# DCDCFinalBoardLayout.net
KiCad netlist of a schematic drawn in EAGLE
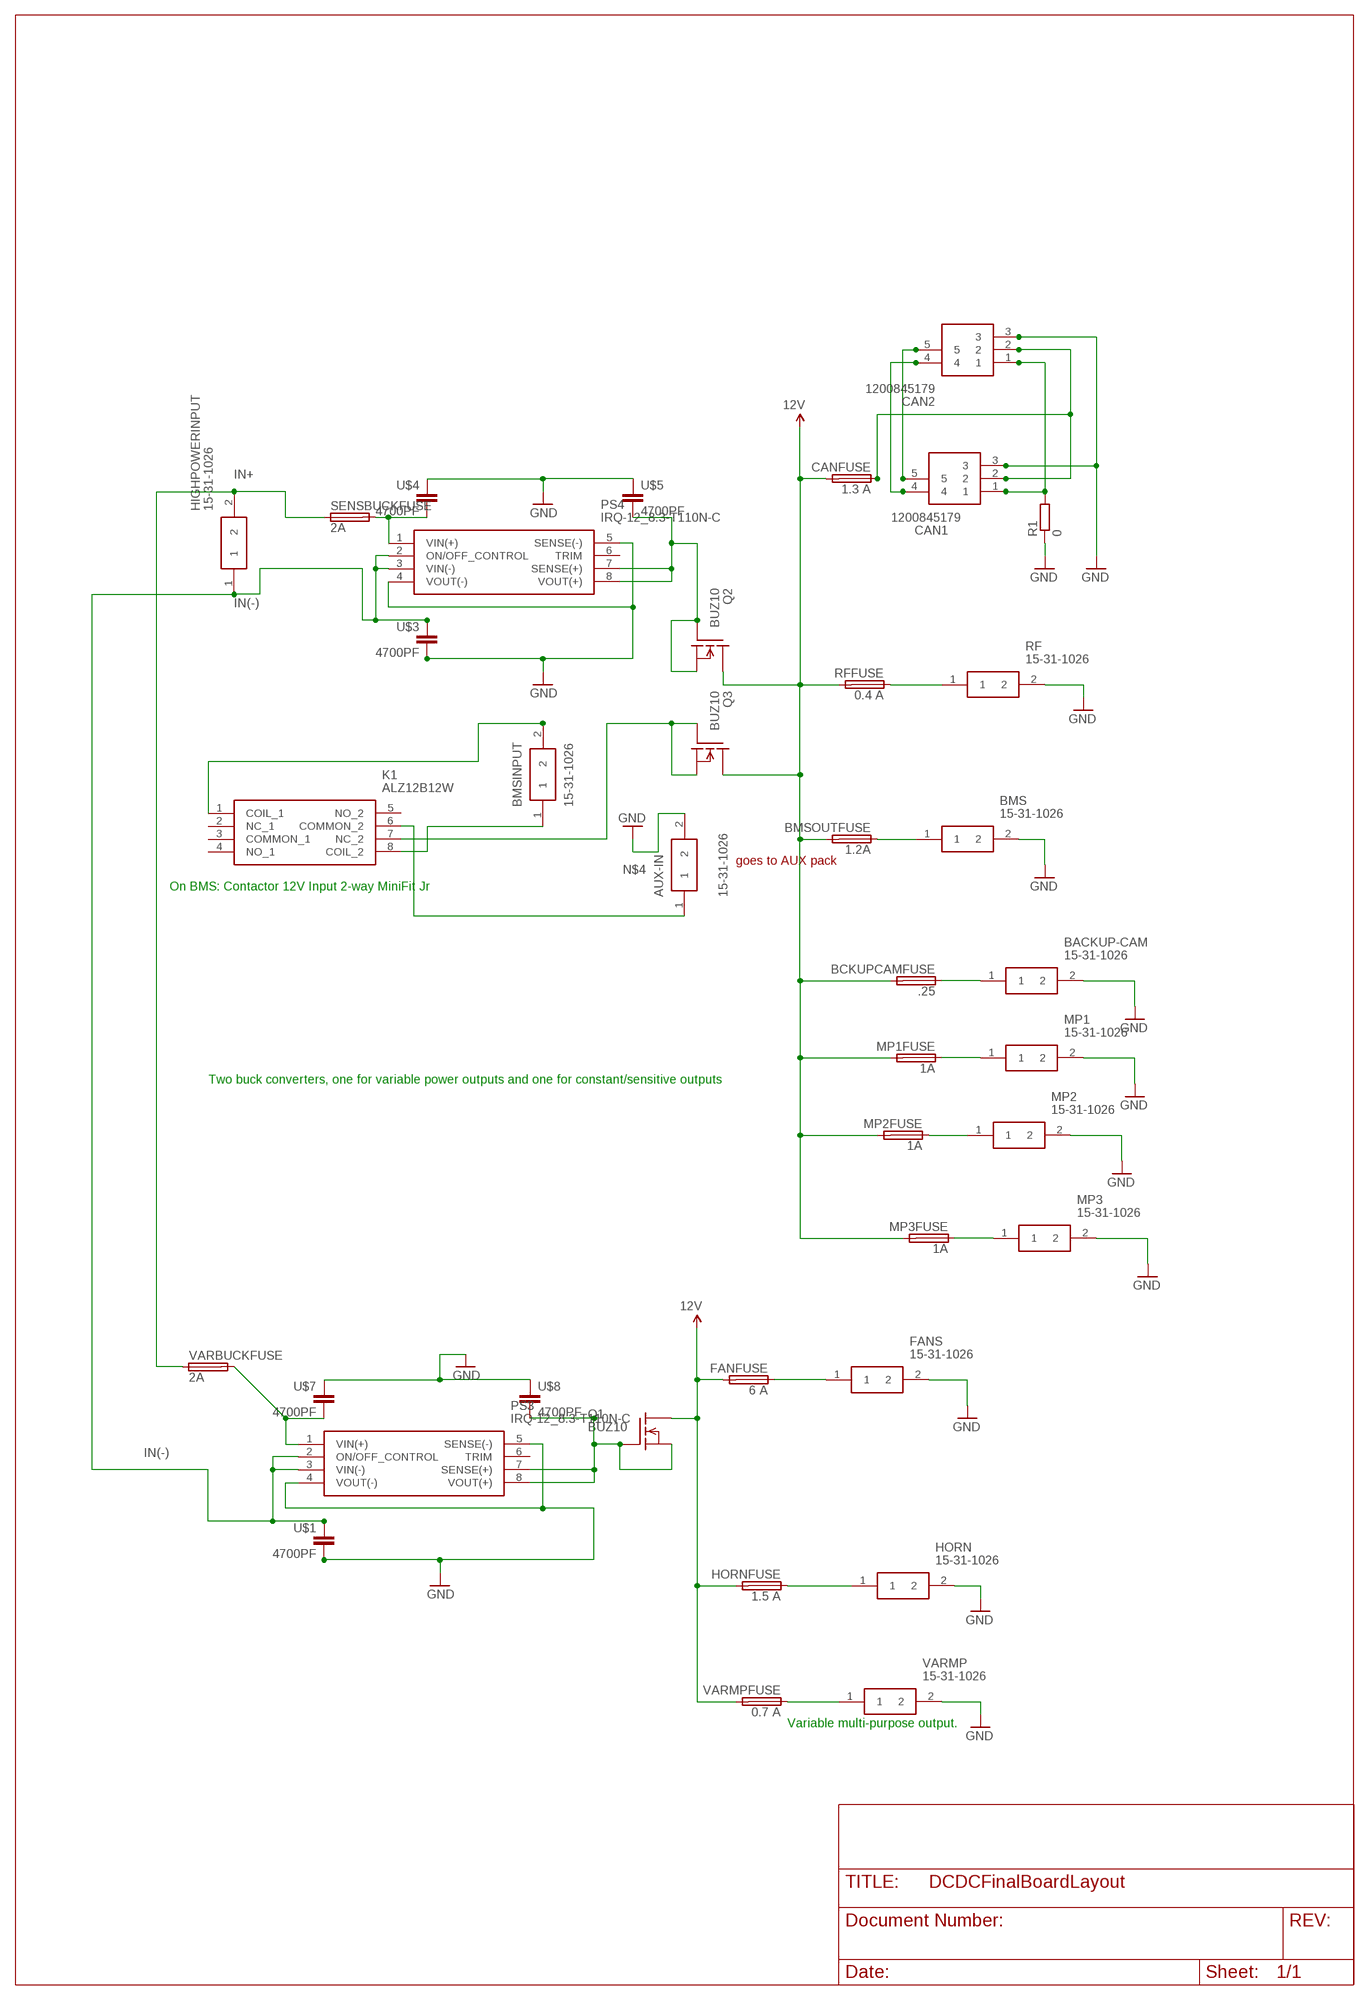
[diagram p0: schematic, sheet 1]

(export (version "E")
  (design (tool "Eeschema 10.0.6"))
  (components
    (comp (ref "AUX-IN")
      (value "15-31-1026")
      (footprint "eagle-import:15311026")
      (fields (field (name "MOUSER_PART_NUMBER") "538-15-31-1026"))
      (libsource (lib "eagle-import") (part "15-31-1026"))
    )
    (comp (ref "BACKUP-CAM")
      (value "15-31-1026")
      (footprint "eagle-import:15311026")
      (fields (field (name "MOUSER_PART_NUMBER") "538-15-31-1026"))
      (libsource (lib "eagle-import") (part "15-31-1026"))
    )
    (comp (ref "BCKUPCAMFUSE")
      (value ".25")
      (footprint "eagle-import:OMNIBLOK")
      (libsource (lib "eagle-import") (part "SMD-MICRO-FUSE-BLOCK"))
    )
    (comp (ref "BMS")
      (value "15-31-1026")
      (footprint "eagle-import:15311026")
      (fields (field (name "MOUSER_PART_NUMBER") "538-15-31-1026"))
      (libsource (lib "eagle-import") (part "15-31-1026"))
    )
    (comp (ref "BMSINPUT")
      (value "15-31-1026")
      (footprint "eagle-import:15311026")
      (fields (field (name "MOUSER_PART_NUMBER") "538-15-31-1026"))
      (libsource (lib "eagle-import") (part "15-31-1026"))
    )
    (comp (ref "BMSOUTFUSE")
      (value "1.2A")
      (footprint "eagle-import:OMNIBLOK")
      (libsource (lib "eagle-import") (part "SMD-MICRO-FUSE-BLOCK"))
    )
    (comp (ref "CAN1")
      (value "1200845179")
      (footprint "eagle-import:1200845179")
      (fields (field (name "MOUSER_PART_NUMBER") "538-1200845179"))
      (libsource (lib "eagle-import") (part "1200845179"))
    )
    (comp (ref "CAN2")
      (value "1200845179")
      (footprint "eagle-import:1200845179")
      (fields (field (name "MOUSER_PART_NUMBER") "538-1200845179"))
      (libsource (lib "eagle-import") (part "1200845179"))
    )
    (comp (ref "CANFUSE")
      (value "1.3 A")
      (footprint "eagle-import:OMNIBLOK")
      (libsource (lib "eagle-import") (part "SMD-MICRO-FUSE-BLOCK"))
    )
    (comp (ref "FANFUSE")
      (value "6 A")
      (footprint "eagle-import:OMNIBLOK")
      (libsource (lib "eagle-import") (part "SMD-MICRO-FUSE-BLOCK"))
    )
    (comp (ref "FANS")
      (value "15-31-1026")
      (footprint "eagle-import:15311026")
      (fields (field (name "MOUSER_PART_NUMBER") "538-15-31-1026"))
      (libsource (lib "eagle-import") (part "15-31-1026"))
    )
    (comp (ref "HIGHPOWERINPUT")
      (value "15-31-1026")
      (footprint "eagle-import:15311026")
      (fields (field (name "MOUSER_PART_NUMBER") "538-15-31-1026"))
      (libsource (lib "eagle-import") (part "15-31-1026"))
    )
    (comp (ref "HORN")
      (value "15-31-1026")
      (footprint "eagle-import:15311026")
      (fields (field (name "MOUSER_PART_NUMBER") "538-15-31-1026"))
      (libsource (lib "eagle-import") (part "15-31-1026"))
    )
    (comp (ref "HORNFUSE")
      (value "1.5 A")
      (footprint "eagle-import:OMNIBLOK")
      (libsource (lib "eagle-import") (part "SMD-MICRO-FUSE-BLOCK"))
    )
    (comp (ref "K1")
      (value "ALZ12B12W")
      (footprint "eagle-import:ALZ12B12W")
      (libsource (lib "eagle-import") (part "ALZ12B12W"))
    )
    (comp (ref "MP1")
      (value "15-31-1026")
      (footprint "eagle-import:15311026")
      (fields (field (name "MOUSER_PART_NUMBER") "538-15-31-1026"))
      (libsource (lib "eagle-import") (part "15-31-1026"))
    )
    (comp (ref "MP1FUSE")
      (value "1A")
      (footprint "eagle-import:OMNIBLOK")
      (libsource (lib "eagle-import") (part "SMD-MICRO-FUSE-BLOCK"))
    )
    (comp (ref "MP2")
      (value "15-31-1026")
      (footprint "eagle-import:15311026")
      (fields (field (name "MOUSER_PART_NUMBER") "538-15-31-1026"))
      (libsource (lib "eagle-import") (part "15-31-1026"))
    )
    (comp (ref "MP2FUSE")
      (value "1A")
      (footprint "eagle-import:OMNIBLOK")
      (libsource (lib "eagle-import") (part "SMD-MICRO-FUSE-BLOCK"))
    )
    (comp (ref "MP3")
      (value "15-31-1026")
      (footprint "eagle-import:15311026")
      (fields (field (name "MOUSER_PART_NUMBER") "538-15-31-1026"))
      (libsource (lib "eagle-import") (part "15-31-1026"))
    )
    (comp (ref "MP3FUSE")
      (value "1A")
      (footprint "eagle-import:OMNIBLOK")
      (libsource (lib "eagle-import") (part "SMD-MICRO-FUSE-BLOCK"))
    )
    (comp (ref "PS3")
      (value "IRQ-12_8.3-T110N-C")
      (footprint "eagle-import:IRQ1283T110NC")
      (fields
        (field (name "MANUFACTURER_PART_NUMBER") "IRQ-12/8.3-T110N-C")
        (field (name "MOUSER_PART_NUMBER") "580-IRQ-12/8.3T110NC")
      )
      (libsource (lib "eagle-import") (part "IRQ-12_8.3-T110N-C"))
    )
    (comp (ref "PS4")
      (value "IRQ-12_8.3-T110N-C")
      (footprint "eagle-import:IRQ1283T110NC")
      (fields
        (field (name "MANUFACTURER_PART_NUMBER") "IRQ-12/8.3-T110N-C")
        (field (name "MOUSER_PART_NUMBER") "580-IRQ-12/8.3T110NC")
      )
      (libsource (lib "eagle-import") (part "IRQ-12_8.3-T110N-C"))
    )
    (comp (ref "Q1")
      (value "BUZ10")
      (footprint "eagle-import:TO220")
      (libsource (lib "eagle-import") (part "BUZ10"))
    )
    (comp (ref "Q2")
      (value "BUZ10")
      (footprint "eagle-import:TO220")
      (libsource (lib "eagle-import") (part "BUZ10"))
    )
    (comp (ref "Q3")
      (value "BUZ10")
      (footprint "eagle-import:TO220")
      (libsource (lib "eagle-import") (part "BUZ10"))
    )
    (comp (ref "R1") (value "0") (footprint "eagle-import:R0805") (libsource (lib "eagle-import") (part "R")))
    (comp (ref "RF")
      (value "15-31-1026")
      (footprint "eagle-import:15311026")
      (fields (field (name "MOUSER_PART_NUMBER") "538-15-31-1026"))
      (libsource (lib "eagle-import") (part "15-31-1026"))
    )
    (comp (ref "RFFUSE")
      (value "0.4 A")
      (footprint "eagle-import:OMNIBLOK")
      (libsource (lib "eagle-import") (part "SMD-MICRO-FUSE-BLOCK"))
    )
    (comp (ref "SENSBUCKFUSE")
      (value "2A")
      (footprint "eagle-import:OMNIBLOK")
      (libsource (lib "eagle-import") (part "SMD-MICRO-FUSE-BLOCK"))
    )
    (comp (ref "U$1")
      (value "4700PF")
      (footprint "eagle-import:Y2_CAP")
      (libsource (lib "eagle-import") (part "4700PF"))
    )
    (comp (ref "U$3")
      (value "4700PF")
      (footprint "eagle-import:Y2_CAP")
      (libsource (lib "eagle-import") (part "4700PF"))
    )
    (comp (ref "U$4")
      (value "4700PF")
      (footprint "eagle-import:Y2_CAP")
      (libsource (lib "eagle-import") (part "4700PF"))
    )
    (comp (ref "U$5")
      (value "4700PF")
      (footprint "eagle-import:Y2_CAP")
      (libsource (lib "eagle-import") (part "4700PF"))
    )
    (comp (ref "U$7")
      (value "4700PF")
      (footprint "eagle-import:Y2_CAP")
      (libsource (lib "eagle-import") (part "4700PF"))
    )
    (comp (ref "U$8")
      (value "4700PF")
      (footprint "eagle-import:Y2_CAP")
      (libsource (lib "eagle-import") (part "4700PF"))
    )
    (comp (ref "VARBUCKFUSE")
      (value "2A")
      (footprint "eagle-import:OMNIBLOK")
      (libsource (lib "eagle-import") (part "SMD-MICRO-FUSE-BLOCK"))
    )
    (comp (ref "VARMP")
      (value "15-31-1026")
      (footprint "eagle-import:15311026")
      (fields (field (name "MOUSER_PART_NUMBER") "538-15-31-1026"))
      (libsource (lib "eagle-import") (part "15-31-1026"))
    )
    (comp (ref "VARMPFUSE")
      (value "0.7 A")
      (footprint "eagle-import:OMNIBLOK")
      (libsource (lib "eagle-import") (part "SMD-MICRO-FUSE-BLOCK"))
    )
  )
  (nets
    (net (code "1") (name "/IN(-)") (class "Default")
      (node (ref "HIGHPOWERINPUT") (pin "1") (pinfunction "1_1") (pintype "bidirectional"))
      (node (ref "PS3") (pin "2") (pinfunction "ON/OFF_CONTROL_2") (pintype "bidirectional"))
      (node (ref "PS3") (pin "3") (pinfunction "VIN(-)_3") (pintype "bidirectional"))
      (node (ref "PS4") (pin "2") (pinfunction "ON/OFF_CONTROL_2") (pintype "bidirectional"))
      (node (ref "PS4") (pin "3") (pinfunction "VIN(-)_3") (pintype "bidirectional"))
      (node (ref "U$1") (pin "P$1") (pinfunction "1_P$1") (pintype "passive"))
      (node (ref "U$3") (pin "P$1") (pinfunction "1_P$1") (pintype "passive"))
    )
    (net (code "2") (name "/IN+") (class "Default")
      (node (ref "HIGHPOWERINPUT") (pin "2") (pinfunction "2_2") (pintype "bidirectional"))
      (node (ref "SENSBUCKFUSE") (pin "P$1") (pinfunction "1_P$1") (pintype "passive"))
      (node (ref "VARBUCKFUSE") (pin "P$1") (pinfunction "1_P$1") (pintype "passive"))
    )
    (net (code "3") (name "/N$4") (class "Default")
      (node (ref "BMSINPUT") (pin "2") (pinfunction "2_2") (pintype "bidirectional"))
      (node (ref "K1") (pin "1") (pinfunction "COIL_1_1") (pintype "bidirectional"))
      (node (ref "K1") (pin "7") (pinfunction "NC_2_7") (pintype "bidirectional"))
      (node (ref "Q3") (pin "1") (pinfunction "G_1") (pintype "passive"))
      (node (ref "Q3") (pin "3") (pinfunction "S_3") (pintype "passive"))
    )
    (net (code "4") (name "12V") (class "Default")
      (node (ref "BCKUPCAMFUSE") (pin "P$2") (pinfunction "2_P$2") (pintype "passive"))
      (node (ref "BMSOUTFUSE") (pin "P$2") (pinfunction "2_P$2") (pintype "passive"))
      (node (ref "CANFUSE") (pin "P$2") (pinfunction "2_P$2") (pintype "passive"))
      (node (ref "FANFUSE") (pin "P$2") (pinfunction "2_P$2") (pintype "passive"))
      (node (ref "HORNFUSE") (pin "P$2") (pinfunction "2_P$2") (pintype "passive"))
      (node (ref "MP1FUSE") (pin "P$2") (pinfunction "2_P$2") (pintype "passive"))
      (node (ref "MP2FUSE") (pin "P$2") (pinfunction "2_P$2") (pintype "passive"))
      (node (ref "MP3FUSE") (pin "P$2") (pinfunction "2_P$2") (pintype "passive"))
      (node (ref "Q1") (pin "2") (pinfunction "D_2") (pintype "passive"))
      (node (ref "Q2") (pin "2") (pinfunction "D_2") (pintype "passive"))
      (node (ref "Q3") (pin "2") (pinfunction "D_2") (pintype "passive"))
      (node (ref "RFFUSE") (pin "P$2") (pinfunction "2_P$2") (pintype "passive"))
      (node (ref "VARMPFUSE") (pin "P$2") (pinfunction "2_P$2") (pintype "passive"))
    )
    (net (code "5") (name "GND") (class "Default")
      (node (ref "AUX-IN") (pin "2") (pinfunction "2_2") (pintype "bidirectional"))
      (node (ref "BACKUP-CAM") (pin "2") (pinfunction "2_2") (pintype "bidirectional"))
      (node (ref "BMS") (pin "2") (pinfunction "2_2") (pintype "bidirectional"))
      (node (ref "CAN1") (pin "3") (pinfunction "3_3") (pintype "bidirectional"))
      (node (ref "CAN2") (pin "3") (pinfunction "3_3") (pintype "bidirectional"))
      (node (ref "FANS") (pin "2") (pinfunction "2_2") (pintype "bidirectional"))
      (node (ref "HORN") (pin "2") (pinfunction "2_2") (pintype "bidirectional"))
      (node (ref "MP1") (pin "2") (pinfunction "2_2") (pintype "bidirectional"))
      (node (ref "MP2") (pin "2") (pinfunction "2_2") (pintype "bidirectional"))
      (node (ref "MP3") (pin "2") (pinfunction "2_2") (pintype "bidirectional"))
      (node (ref "PS3") (pin "4") (pinfunction "VOUT(-)_4") (pintype "bidirectional"))
      (node (ref "PS3") (pin "5") (pinfunction "SENSE(-)_5") (pintype "bidirectional"))
      (node (ref "PS4") (pin "4") (pinfunction "VOUT(-)_4") (pintype "bidirectional"))
      (node (ref "PS4") (pin "5") (pinfunction "SENSE(-)_5") (pintype "bidirectional"))
      (node (ref "R1") (pin "1") (pinfunction "1_1") (pintype "passive"))
      (node (ref "RF") (pin "2") (pinfunction "2_2") (pintype "bidirectional"))
      (node (ref "U$1") (pin "P$2") (pinfunction "2_P$2") (pintype "passive"))
      (node (ref "U$3") (pin "P$2") (pinfunction "2_P$2") (pintype "passive"))
      (node (ref "U$4") (pin "P$1") (pinfunction "1_P$1") (pintype "passive"))
      (node (ref "U$5") (pin "P$1") (pinfunction "1_P$1") (pintype "passive"))
      (node (ref "U$7") (pin "P$1") (pinfunction "1_P$1") (pintype "passive"))
      (node (ref "U$8") (pin "P$1") (pinfunction "1_P$1") (pintype "passive"))
      (node (ref "VARMP") (pin "2") (pinfunction "2_2") (pintype "bidirectional"))
    )
    (net (code "6") (name "Net-(BCKUPCAMFUSE-1)") (class "Default")
      (node (ref "BACKUP-CAM") (pin "1") (pinfunction "1_1") (pintype "bidirectional"))
      (node (ref "BCKUPCAMFUSE") (pin "P$1") (pinfunction "1_P$1") (pintype "passive"))
    )
    (net (code "7") (name "Net-(BMSOUTFUSE-1)") (class "Default")
      (node (ref "BMS") (pin "1") (pinfunction "1_1") (pintype "bidirectional"))
      (node (ref "BMSOUTFUSE") (pin "P$1") (pinfunction "1_P$1") (pintype "passive"))
    )
    (net (code "8") (name "Net-(CAN1-Pad1)") (class "Default")
      (node (ref "CAN1") (pin "1") (pinfunction "1_1") (pintype "bidirectional"))
      (node (ref "CAN2") (pin "1") (pinfunction "1_1") (pintype "bidirectional"))
      (node (ref "R1") (pin "2") (pinfunction "2_2") (pintype "passive"))
    )
    (net (code "9") (name "Net-(CAN1-Pad4)") (class "Default")
      (node (ref "CAN1") (pin "4") (pinfunction "4_4") (pintype "bidirectional"))
      (node (ref "CAN2") (pin "4") (pinfunction "4_4") (pintype "bidirectional"))
    )
    (net (code "10") (name "Net-(CAN1-Pad5)") (class "Default")
      (node (ref "CAN1") (pin "5") (pinfunction "5_5") (pintype "bidirectional"))
      (node (ref "CAN2") (pin "5") (pinfunction "5_5") (pintype "bidirectional"))
    )
    (net (code "11") (name "Net-(CANFUSE-1)") (class "Default")
      (node (ref "CAN1") (pin "2") (pinfunction "2_2") (pintype "bidirectional"))
      (node (ref "CAN2") (pin "2") (pinfunction "2_2") (pintype "bidirectional"))
      (node (ref "CANFUSE") (pin "P$1") (pinfunction "1_P$1") (pintype "passive"))
    )
    (net (code "12") (name "Net-(FANFUSE-1)") (class "Default")
      (node (ref "FANFUSE") (pin "P$1") (pinfunction "1_P$1") (pintype "passive"))
      (node (ref "FANS") (pin "1") (pinfunction "1_1") (pintype "bidirectional"))
    )
    (net (code "13") (name "Net-(HORNFUSE-1)") (class "Default")
      (node (ref "HORN") (pin "1") (pinfunction "1_1") (pintype "bidirectional"))
      (node (ref "HORNFUSE") (pin "P$1") (pinfunction "1_P$1") (pintype "passive"))
    )
    (net (code "14") (name "Net-(K1-COIL_2)") (class "Default")
      (node (ref "BMSINPUT") (pin "1") (pinfunction "1_1") (pintype "bidirectional"))
      (node (ref "K1") (pin "8") (pinfunction "COIL_2_8") (pintype "bidirectional"))
    )
    (net (code "15") (name "Net-(K1-COMMON_2)") (class "Default")
      (node (ref "AUX-IN") (pin "1") (pinfunction "1_1") (pintype "bidirectional"))
      (node (ref "K1") (pin "6") (pinfunction "COMMON_2_6") (pintype "bidirectional"))
    )
    (net (code "16") (name "Net-(MP1FUSE-1)") (class "Default")
      (node (ref "MP1") (pin "1") (pinfunction "1_1") (pintype "bidirectional"))
      (node (ref "MP1FUSE") (pin "P$1") (pinfunction "1_P$1") (pintype "passive"))
    )
    (net (code "17") (name "Net-(MP2FUSE-1)") (class "Default")
      (node (ref "MP2") (pin "1") (pinfunction "1_1") (pintype "bidirectional"))
      (node (ref "MP2FUSE") (pin "P$1") (pinfunction "1_P$1") (pintype "passive"))
    )
    (net (code "18") (name "Net-(MP3FUSE-1)") (class "Default")
      (node (ref "MP3") (pin "1") (pinfunction "1_1") (pintype "bidirectional"))
      (node (ref "MP3FUSE") (pin "P$1") (pinfunction "1_P$1") (pintype "passive"))
    )
    (net (code "19") (name "Net-(PS3-SENSE(+))") (class "Default")
      (node (ref "PS3") (pin "7") (pinfunction "SENSE(+)_7") (pintype "bidirectional"))
      (node (ref "PS3") (pin "8") (pinfunction "VOUT(+)_8") (pintype "bidirectional"))
      (node (ref "Q1") (pin "1") (pinfunction "G_1") (pintype "passive"))
      (node (ref "Q1") (pin "3") (pinfunction "S_3") (pintype "passive"))
      (node (ref "U$8") (pin "P$2") (pinfunction "2_P$2") (pintype "passive"))
    )
    (net (code "20") (name "Net-(PS3-VIN(+))") (class "Default")
      (node (ref "PS3") (pin "1") (pinfunction "VIN(+)_1") (pintype "bidirectional"))
      (node (ref "U$7") (pin "P$2") (pinfunction "2_P$2") (pintype "passive"))
      (node (ref "VARBUCKFUSE") (pin "P$2") (pinfunction "2_P$2") (pintype "passive"))
    )
    (net (code "21") (name "Net-(PS4-SENSE(+))") (class "Default")
      (node (ref "PS4") (pin "7") (pinfunction "SENSE(+)_7") (pintype "bidirectional"))
      (node (ref "PS4") (pin "8") (pinfunction "VOUT(+)_8") (pintype "bidirectional"))
      (node (ref "Q2") (pin "1") (pinfunction "G_1") (pintype "passive"))
      (node (ref "Q2") (pin "3") (pinfunction "S_3") (pintype "passive"))
      (node (ref "U$5") (pin "P$2") (pinfunction "2_P$2") (pintype "passive"))
    )
    (net (code "22") (name "Net-(PS4-VIN(+))") (class "Default")
      (node (ref "PS4") (pin "1") (pinfunction "VIN(+)_1") (pintype "bidirectional"))
      (node (ref "SENSBUCKFUSE") (pin "P$2") (pinfunction "2_P$2") (pintype "passive"))
      (node (ref "U$4") (pin "P$2") (pinfunction "2_P$2") (pintype "passive"))
    )
    (net (code "23") (name "Net-(RFFUSE-1)") (class "Default")
      (node (ref "RF") (pin "1") (pinfunction "1_1") (pintype "bidirectional"))
      (node (ref "RFFUSE") (pin "P$1") (pinfunction "1_P$1") (pintype "passive"))
    )
    (net (code "24") (name "Net-(VARMPFUSE-1)") (class "Default")
      (node (ref "VARMP") (pin "1") (pinfunction "1_1") (pintype "bidirectional"))
      (node (ref "VARMPFUSE") (pin "P$1") (pinfunction "1_P$1") (pintype "passive"))
    )
    (net (code "25") (name "unconnected-(K1-COMMON_1-Pad3)") (class "Default")
      (node (ref "K1") (pin "3") (pinfunction "COMMON_1_3") (pintype "bidirectional"))
    )
    (net (code "26") (name "unconnected-(K1-NC_1-Pad2)") (class "Default")
      (node (ref "K1") (pin "2") (pinfunction "NC_1_2") (pintype "bidirectional"))
    )
    (net (code "27") (name "unconnected-(K1-NO_1-Pad4)") (class "Default")
      (node (ref "K1") (pin "4") (pinfunction "NO_1_4") (pintype "bidirectional"))
    )
    (net (code "28") (name "unconnected-(K1-NO_2-Pad5)") (class "Default")
      (node (ref "K1") (pin "5") (pinfunction "NO_2_5") (pintype "bidirectional"))
    )
    (net (code "29") (name "unconnected-(PS3-TRIM-Pad6)") (class "Default")
      (node (ref "PS3") (pin "6") (pinfunction "TRIM_6") (pintype "bidirectional"))
    )
    (net (code "30") (name "unconnected-(PS4-TRIM-Pad6)") (class "Default")
      (node (ref "PS4") (pin "6") (pinfunction "TRIM_6") (pintype "bidirectional"))
    )
  )
)
